# rentalito.net
KiCad netlist of a schematic drawn in EAGLE
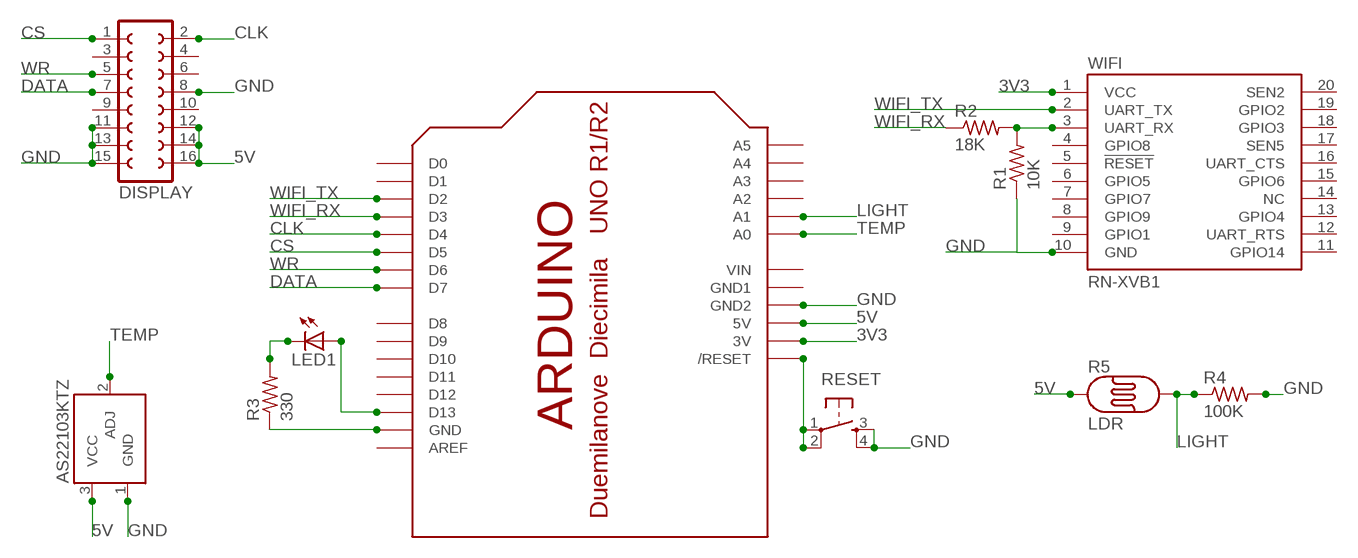
[diagram p0: schematic, sheet 1]

(export (version "E")
  (design (tool "Eeschema 10.0.6"))
  (components
    (comp (ref "AS22103KTZ")
      (value "TEMPERATURE-SENSOR")
      (footprint "eagle-import:TO-92")
      (libsource (lib "eagle-import") (part "TEMPERATURE-SENSOR"))
    )
    (comp (ref "DISPLAY")
      (value "FE08-2")
      (footprint "eagle-import:FE08-2")
      (libsource (lib "eagle-import") (part "FE08-2"))
    )
    (comp (ref "LED1")
      (value "LED5MM")
      (footprint "eagle-import:LED5MM")
      (libsource (lib "eagle-import") (part "LED5MM"))
    )
    (comp (ref "R1")
      (value "10K")
      (footprint "eagle-import:0204_7")
      (libsource (lib "eagle-import") (part "R-US_0204/7"))
    )
    (comp (ref "R2")
      (value "18K")
      (footprint "eagle-import:0204_7")
      (libsource (lib "eagle-import") (part "R-US_0204/7"))
    )
    (comp (ref "R3")
      (value "330")
      (footprint "eagle-import:0204_7")
      (libsource (lib "eagle-import") (part "R-US_0204/7"))
    )
    (comp (ref "R4")
      (value "100K")
      (footprint "eagle-import:0204_7")
      (libsource (lib "eagle-import") (part "R-US_0204/7"))
    )
    (comp (ref "R5")
      (value "LDR")
      (footprint "eagle-import:PHOTOCELL")
      (libsource (lib "eagle-import") (part "PHOTOCELLPTH"))
    )
    (comp (ref "RESET")
      (value "TAC_SWITCHPTH")
      (footprint "eagle-import:TACTILE-PTH")
      (libsource (lib "eagle-import") (part "TAC_SWITCHPTH"))
    )
    (comp (ref "U$1")
      (value "ARDUINOUNO")
      (footprint "eagle-import:ARDUINO")
      (libsource (lib "eagle-import") (part "ARDUINOUNO"))
    )
    (comp (ref "WIFI")
      (value "RN-XVB1")
      (footprint "eagle-import:XBEE")
      (libsource (lib "eagle-import") (part "RN-XVB1"))
    )
  )
  (nets
    (net (code "1") (name "/3V3") (class "Default")
      (node (ref "U$1") (pin "3V") (pinfunction "3V_3V") (pintype "power_in"))
      (node (ref "WIFI") (pin "1") (pinfunction "VCC_1") (pintype "power_in"))
    )
    (net (code "2") (name "/5V") (class "Default")
      (node (ref "AS22103KTZ") (pin "3") (pinfunction "VCC_3") (pintype "bidirectional"))
      (node (ref "DISPLAY") (pin "12") (pinfunction "12_12") (pintype "passive"))
      (node (ref "DISPLAY") (pin "14") (pinfunction "14_14") (pintype "passive"))
      (node (ref "DISPLAY") (pin "16") (pinfunction "16_16") (pintype "passive"))
      (node (ref "R5") (pin "1") (pinfunction "P$1_1") (pintype "bidirectional"))
      (node (ref "U$1") (pin "5V") (pinfunction "5V_5V") (pintype "power_in"))
    )
    (net (code "3") (name "/CLK") (class "Default")
      (node (ref "DISPLAY") (pin "2") (pinfunction "2_2") (pintype "passive"))
      (node (ref "U$1") (pin "D4") (pinfunction "D4_D4") (pintype "bidirectional"))
    )
    (net (code "4") (name "/CS") (class "Default")
      (node (ref "DISPLAY") (pin "1") (pinfunction "1_1") (pintype "passive"))
      (node (ref "U$1") (pin "D5") (pinfunction "D5_D5") (pintype "bidirectional"))
    )
    (net (code "5") (name "/DATA") (class "Default")
      (node (ref "DISPLAY") (pin "7") (pinfunction "7_7") (pintype "passive"))
      (node (ref "U$1") (pin "D7") (pinfunction "D7_D7") (pintype "bidirectional"))
    )
    (net (code "6") (name "/GND") (class "Default")
      (node (ref "AS22103KTZ") (pin "1") (pinfunction "GND_1") (pintype "bidirectional"))
      (node (ref "DISPLAY") (pin "11") (pinfunction "11_11") (pintype "passive"))
      (node (ref "DISPLAY") (pin "13") (pinfunction "13_13") (pintype "passive"))
      (node (ref "DISPLAY") (pin "15") (pinfunction "15_15") (pintype "passive"))
      (node (ref "DISPLAY") (pin "8") (pinfunction "8_8") (pintype "passive"))
      (node (ref "R1") (pin "1") (pinfunction "1_1") (pintype "passive"))
      (node (ref "R4") (pin "2") (pinfunction "2_2") (pintype "passive"))
      (node (ref "RESET") (pin "3") (pinfunction "3_3") (pintype "passive"))
      (node (ref "RESET") (pin "4") (pinfunction "4_4") (pintype "passive"))
      (node (ref "U$1") (pin "GND2") (pinfunction "GND2_GND2") (pintype "power_in"))
      (node (ref "WIFI") (pin "10") (pinfunction "GND_10") (pintype "power_in"))
    )
    (net (code "7") (name "/GND1") (class "Default")
      (node (ref "U$1") (pin "GND1") (pinfunction "GND1_GND1") (pintype "power_in"))
    )
    (net (code "8") (name "/LIGHT") (class "Default")
      (node (ref "R4") (pin "1") (pinfunction "1_1") (pintype "passive"))
      (node (ref "R5") (pin "2") (pinfunction "P$2_2") (pintype "bidirectional"))
      (node (ref "U$1") (pin "A1") (pinfunction "A1_A1") (pintype "bidirectional"))
    )
    (net (code "9") (name "/TEMP") (class "Default")
      (node (ref "AS22103KTZ") (pin "2") (pinfunction "ADJ_2") (pintype "bidirectional"))
      (node (ref "U$1") (pin "A0") (pinfunction "A0_A0") (pintype "bidirectional"))
    )
    (net (code "10") (name "/VIN") (class "Default")
      (node (ref "U$1") (pin "VIN") (pinfunction "VIN_VIN") (pintype "power_in"))
    )
    (net (code "11") (name "/WIFI_RX") (class "Default")
      (node (ref "R2") (pin "1") (pinfunction "1_1") (pintype "passive"))
      (node (ref "U$1") (pin "D3") (pinfunction "D3_D3") (pintype "bidirectional"))
    )
    (net (code "12") (name "/WIFI_TX") (class "Default")
      (node (ref "U$1") (pin "D2") (pinfunction "D2_D2") (pintype "bidirectional"))
      (node (ref "WIFI") (pin "2") (pinfunction "UART_TX_2") (pintype "output"))
    )
    (net (code "13") (name "/WR") (class "Default")
      (node (ref "DISPLAY") (pin "5") (pinfunction "5_5") (pintype "passive"))
      (node (ref "U$1") (pin "D6") (pinfunction "D6_D6") (pintype "bidirectional"))
    )
    (net (code "14") (name "Net-(LED1-C)") (class "Default")
      (node (ref "LED1") (pin "K") (pinfunction "C_K") (pintype "passive"))
      (node (ref "R3") (pin "2") (pinfunction "2_2") (pintype "passive"))
    )
    (net (code "15") (name "Net-(LED1-PadA)") (class "Default")
      (node (ref "LED1") (pin "A") (pinfunction "A_A") (pintype "passive"))
      (node (ref "U$1") (pin "D13") (pinfunction "D13_D13") (pintype "bidirectional"))
    )
    (net (code "16") (name "Net-(R3-Pad1)") (class "Default")
      (node (ref "R3") (pin "1") (pinfunction "1_1") (pintype "passive"))
      (node (ref "U$1") (pin "GND") (pinfunction "GND_GND") (pintype "power_in"))
    )
    (net (code "17") (name "Net-(U$1-{slash}RESET)") (class "Default")
      (node (ref "RESET") (pin "1") (pinfunction "1_1") (pintype "passive"))
      (node (ref "RESET") (pin "2") (pinfunction "2_2") (pintype "passive"))
      (node (ref "U$1") (pin "RESET") (pinfunction "/RESET_RESET") (pintype "bidirectional"))
    )
    (net (code "18") (name "Net-(WIFI-UART_RX)") (class "Default")
      (node (ref "R1") (pin "2") (pinfunction "2_2") (pintype "passive"))
      (node (ref "R2") (pin "2") (pinfunction "2_2") (pintype "passive"))
      (node (ref "WIFI") (pin "3") (pinfunction "UART_RX_3") (pintype "input"))
    )
    (net (code "19") (name "unconnected-(DISPLAY-Pad3)") (class "Default")
      (node (ref "DISPLAY") (pin "3") (pinfunction "3_3") (pintype "passive"))
    )
    (net (code "20") (name "unconnected-(DISPLAY-Pad4)") (class "Default")
      (node (ref "DISPLAY") (pin "4") (pinfunction "4_4") (pintype "passive"))
    )
    (net (code "21") (name "unconnected-(DISPLAY-Pad6)") (class "Default")
      (node (ref "DISPLAY") (pin "6") (pinfunction "6_6") (pintype "passive"))
    )
    (net (code "22") (name "unconnected-(DISPLAY-Pad9)") (class "Default")
      (node (ref "DISPLAY") (pin "9") (pinfunction "9_9") (pintype "passive"))
    )
    (net (code "23") (name "unconnected-(DISPLAY-Pad10)") (class "Default")
      (node (ref "DISPLAY") (pin "10") (pinfunction "10_10") (pintype "passive"))
    )
    (net (code "24") (name "unconnected-(U$1-PadA2)") (class "Default")
      (node (ref "U$1") (pin "A2") (pinfunction "A2_A2") (pintype "bidirectional"))
    )
    (net (code "25") (name "unconnected-(U$1-PadA3)") (class "Default")
      (node (ref "U$1") (pin "A3") (pinfunction "A3_A3") (pintype "bidirectional"))
    )
    (net (code "26") (name "unconnected-(U$1-PadA4)") (class "Default")
      (node (ref "U$1") (pin "A4") (pinfunction "A4_A4") (pintype "bidirectional"))
    )
    (net (code "27") (name "unconnected-(U$1-PadA5)") (class "Default")
      (node (ref "U$1") (pin "A5") (pinfunction "A5_A5") (pintype "bidirectional"))
    )
    (net (code "28") (name "unconnected-(U$1-PadAREF)") (class "Default")
      (node (ref "U$1") (pin "AREF") (pinfunction "AREF_AREF") (pintype "bidirectional"))
    )
    (net (code "29") (name "unconnected-(U$1-PadD0)") (class "Default")
      (node (ref "U$1") (pin "D0") (pinfunction "D0_D0") (pintype "bidirectional"))
    )
    (net (code "30") (name "unconnected-(U$1-PadD1)") (class "Default")
      (node (ref "U$1") (pin "D1") (pinfunction "D1_D1") (pintype "bidirectional"))
    )
    (net (code "31") (name "unconnected-(U$1-PadD8)") (class "Default")
      (node (ref "U$1") (pin "D8") (pinfunction "D8_D8") (pintype "bidirectional"))
    )
    (net (code "32") (name "unconnected-(U$1-PadD9)") (class "Default")
      (node (ref "U$1") (pin "D9") (pinfunction "D9_D9") (pintype "bidirectional"))
    )
    (net (code "33") (name "unconnected-(U$1-PadD10)") (class "Default")
      (node (ref "U$1") (pin "D10") (pinfunction "D10_D10") (pintype "bidirectional"))
    )
    (net (code "34") (name "unconnected-(U$1-PadD11)") (class "Default")
      (node (ref "U$1") (pin "D11") (pinfunction "D11_D11") (pintype "bidirectional"))
    )
    (net (code "35") (name "unconnected-(U$1-PadD12)") (class "Default")
      (node (ref "U$1") (pin "D12") (pinfunction "D12_D12") (pintype "bidirectional"))
    )
    (net (code "36") (name "unconnected-(WIFI-GPIO1-Pad9)") (class "Default")
      (node (ref "WIFI") (pin "9") (pinfunction "GPIO1_9") (pintype "bidirectional"))
    )
    (net (code "37") (name "unconnected-(WIFI-GPIO2-Pad19)") (class "Default")
      (node (ref "WIFI") (pin "19") (pinfunction "GPIO2_19") (pintype "bidirectional"))
    )
    (net (code "38") (name "unconnected-(WIFI-GPIO3-Pad18)") (class "Default")
      (node (ref "WIFI") (pin "18") (pinfunction "GPIO3_18") (pintype "bidirectional"))
    )
    (net (code "39") (name "unconnected-(WIFI-GPIO4-Pad13)") (class "Default")
      (node (ref "WIFI") (pin "13") (pinfunction "GPIO4_13") (pintype "bidirectional"))
    )
    (net (code "40") (name "unconnected-(WIFI-GPIO5-Pad6)") (class "Default")
      (node (ref "WIFI") (pin "6") (pinfunction "GPIO5_6") (pintype "bidirectional"))
    )
    (net (code "41") (name "unconnected-(WIFI-GPIO6-Pad15)") (class "Default")
      (node (ref "WIFI") (pin "15") (pinfunction "GPIO6_15") (pintype "bidirectional"))
    )
    (net (code "42") (name "unconnected-(WIFI-GPIO7-Pad7)") (class "Default")
      (node (ref "WIFI") (pin "7") (pinfunction "GPIO7_7") (pintype "bidirectional"))
    )
    (net (code "43") (name "unconnected-(WIFI-GPIO8-Pad4)") (class "Default")
      (node (ref "WIFI") (pin "4") (pinfunction "GPIO8_4") (pintype "bidirectional"))
    )
    (net (code "44") (name "unconnected-(WIFI-GPIO9-Pad8)") (class "Default")
      (node (ref "WIFI") (pin "8") (pinfunction "GPIO9_8") (pintype "bidirectional"))
    )
    (net (code "45") (name "unconnected-(WIFI-GPIO14-Pad11)") (class "Default")
      (node (ref "WIFI") (pin "11") (pinfunction "GPIO14_11") (pintype "bidirectional"))
    )
    (net (code "46") (name "unconnected-(WIFI-NC-Pad14)") (class "Default")
      (node (ref "WIFI") (pin "14") (pinfunction "NC_14") (pintype "no_connect"))
    )
    (net (code "47") (name "unconnected-(WIFI-SEN2-Pad20)") (class "Default")
      (node (ref "WIFI") (pin "20") (pinfunction "SEN2_20") (pintype "bidirectional"))
    )
    (net (code "48") (name "unconnected-(WIFI-SEN5-Pad17)") (class "Default")
      (node (ref "WIFI") (pin "17") (pinfunction "SEN5_17") (pintype "bidirectional"))
    )
    (net (code "49") (name "unconnected-(WIFI-UART_CTS-Pad16)") (class "Default")
      (node (ref "WIFI") (pin "16") (pinfunction "UART_CTS_16") (pintype "input"))
    )
    (net (code "50") (name "unconnected-(WIFI-UART_RTS-Pad12)") (class "Default")
      (node (ref "WIFI") (pin "12") (pinfunction "UART_RTS_12") (pintype "output"))
    )
    (net (code "51") (name "unconnected-(WIFI-~{RESET}-Pad5)") (class "Default")
      (node (ref "WIFI") (pin "5") (pinfunction "~{RESET}_5") (pintype "input"))
    )
  )
)
